# MCU.net
KiCad netlist of a schematic drawn in Altium Designer
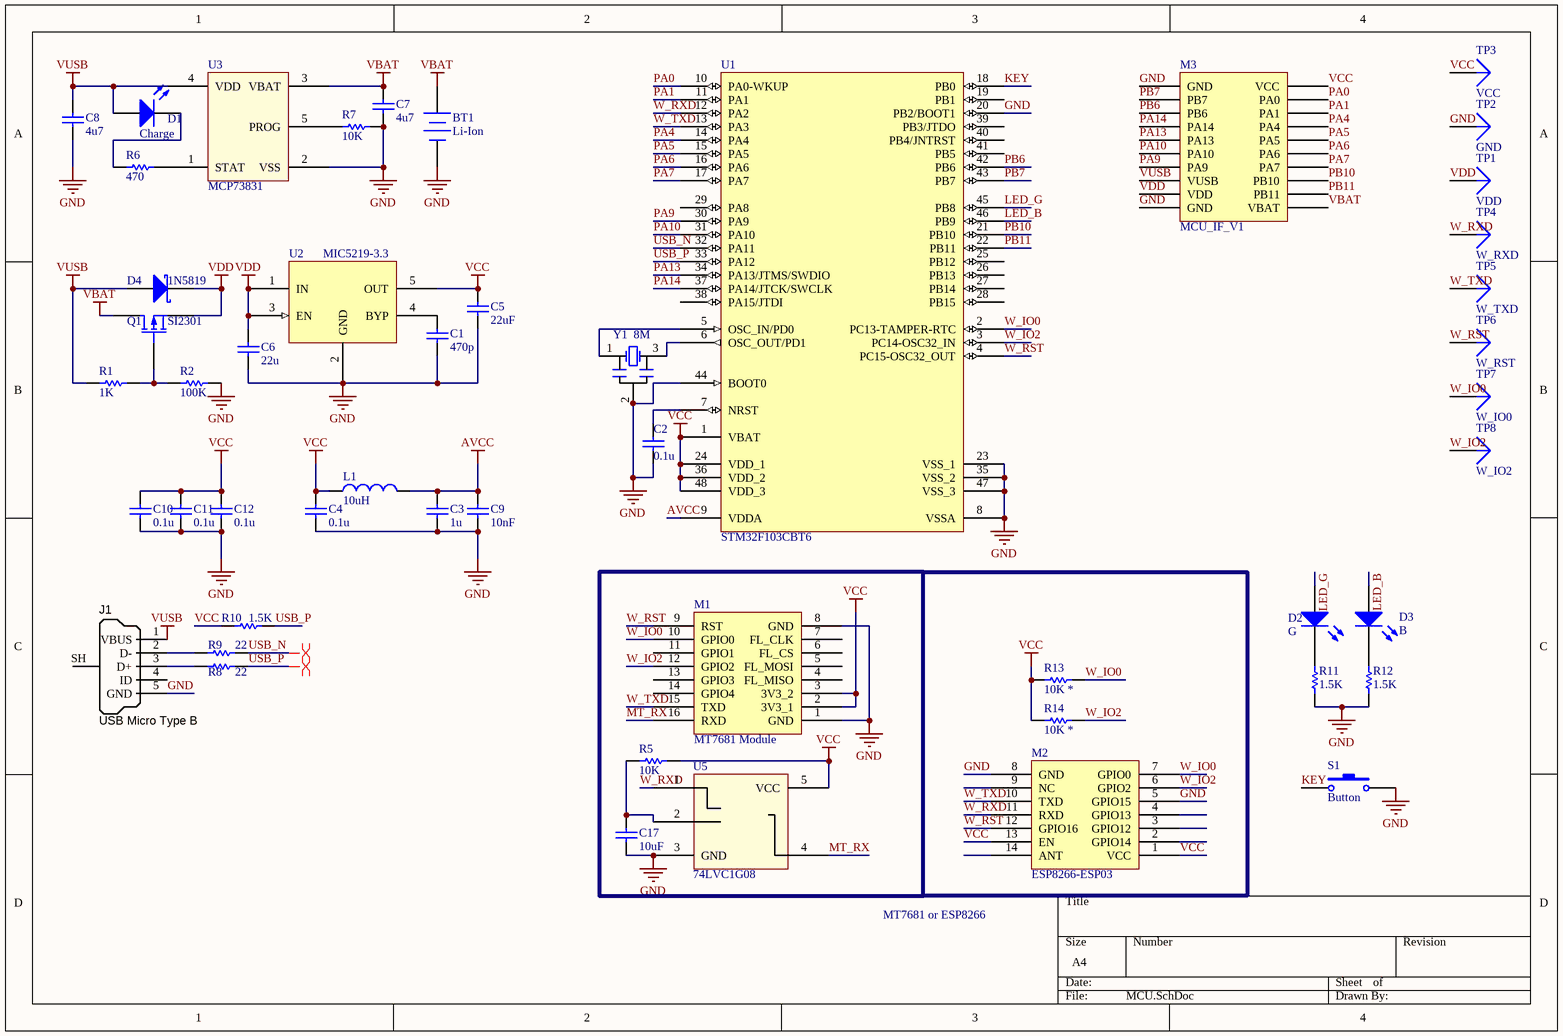
[diagram p0: MCU.SchDoc]

(export (version "E")
  (design (tool "Eeschema 10.0.6"))
  (components
    (comp (ref "BT1")
      (value "Li-Ion")
      (footprint "HDR1X2")
      (description "Multicell Battery")
      (fields (field (name "PUBLISHER") "Altium Limited"))
      (libsource (lib "Miscellaneous Devices") (part "Battery"))
    )
    (comp (ref "C1")
      (value "470p")
      (footprint "C-1608[0603]")
      (description "Capacitor (Semiconductor SIM Model)")
      (fields (field (name "Comment") "Cap Semi") (field (name "PUBLISHER") "Altium Limited"))
      (libsource (lib "Miscellaneous Devices") (part "Cap Semi"))
    )
    (comp (ref "C2")
      (value "0.1u")
      (footprint "C-1608[0603]")
      (description "Capacitor (Semiconductor SIM Model)")
      (fields (field (name "Comment") "Cap Semi") (field (name "PUBLISHER") "Altium Limited"))
      (libsource (lib "Miscellaneous Devices") (part "Cap Semi"))
    )
    (comp (ref "C3")
      (value "1u")
      (footprint "C-1608[0603]")
      (description "Capacitor (Semiconductor SIM Model)")
      (fields (field (name "Comment") "Cap Semi") (field (name "PUBLISHER") "Altium Limited"))
      (libsource (lib "Miscellaneous Devices") (part "Cap Semi"))
    )
    (comp (ref "C4")
      (value "0.1u")
      (footprint "C-1608[0603]")
      (description "Capacitor (Semiconductor SIM Model)")
      (fields (field (name "Comment") "Cap Semi") (field (name "PUBLISHER") "Altium Limited"))
      (libsource (lib "Miscellaneous Devices") (part "Cap Semi"))
    )
    (comp (ref "C5")
      (value "22uF")
      (footprint "C-2012[0805]")
      (description "Capacitor (Semiconductor SIM Model)")
      (fields (field (name "Comment") "Cap Semi") (field (name "PUBLISHER") "Altium Limited"))
      (libsource (lib "Miscellaneous Devices") (part "Cap Semi"))
    )
    (comp (ref "C6")
      (value "22u")
      (footprint "C-2012[0805]")
      (description "Capacitor (Semiconductor SIM Model)")
      (fields (field (name "Comment") "Cap Semi") (field (name "PUBLISHER") "Altium Limited"))
      (libsource (lib "Miscellaneous Devices") (part "Cap Semi"))
    )
    (comp (ref "C7")
      (value "4u7")
      (footprint "C-1608[0603]")
      (description "Capacitor (Semiconductor SIM Model)")
      (fields (field (name "Comment") "Cap Semi") (field (name "PUBLISHER") "Altium Limited"))
      (libsource (lib "Miscellaneous Devices") (part "Cap Semi"))
    )
    (comp (ref "C8")
      (value "4u7")
      (footprint "C-1608[0603]")
      (description "Capacitor (Semiconductor SIM Model)")
      (fields (field (name "Comment") "Cap Semi") (field (name "PUBLISHER") "Altium Limited"))
      (libsource (lib "Miscellaneous Devices") (part "Cap Semi"))
    )
    (comp (ref "C9")
      (value "10nF")
      (footprint "C-1608[0603]")
      (description "Capacitor (Semiconductor SIM Model)")
      (fields (field (name "Comment") "Cap Semi") (field (name "PUBLISHER") "Altium Limited"))
      (libsource (lib "Miscellaneous Devices") (part "Cap Semi"))
    )
    (comp (ref "C10")
      (value "0.1u")
      (footprint "C-1608[0603]")
      (description "Capacitor (Semiconductor SIM Model)")
      (fields (field (name "Comment") "Cap Semi") (field (name "PUBLISHER") "Altium Limited"))
      (libsource (lib "Miscellaneous Devices") (part "Cap Semi"))
    )
    (comp (ref "C11")
      (value "0.1u")
      (footprint "C-1608[0603]")
      (description "Capacitor (Semiconductor SIM Model)")
      (fields (field (name "Comment") "Cap Semi") (field (name "PUBLISHER") "Altium Limited"))
      (libsource (lib "Miscellaneous Devices") (part "Cap Semi"))
    )
    (comp (ref "C12")
      (value "0.1u")
      (footprint "C-1608[0603]")
      (description "Capacitor (Semiconductor SIM Model)")
      (fields (field (name "Comment") "Cap Semi") (field (name "PUBLISHER") "Altium Limited"))
      (libsource (lib "Miscellaneous Devices") (part "Cap Semi"))
    )
    (comp (ref "C17")
      (value "10uF")
      (footprint "C-1608[0603]")
      (description "Capacitor (Semiconductor SIM Model)")
      (fields (field (name "Comment") "Cap Semi") (field (name "PUBLISHER") "Altium Limited"))
      (libsource (lib "Miscellaneous Devices") (part "Cap Semi"))
    )
    (comp (ref "D1")
      (value "Charge")
      (footprint "LED-1608[0603]-R")
      (description "Typical RED, GREEN, YELLOW, AMBER GaAs LED")
      (fields (field (name "PUBLISHER") "Altium Limited"))
      (libsource (lib "Miscellaneous Devices") (part "LED2"))
    )
    (comp (ref "D2")
      (value "G")
      (footprint "LED-1608[0603]-G")
      (description "Typical RED, GREEN, YELLOW, AMBER GaAs LED")
      (fields (field (name "PUBLISHER") "Altium Limited"))
      (libsource (lib "Miscellaneous Devices") (part "LED2"))
    )
    (comp (ref "D3")
      (value "B")
      (footprint "LED-1608[0603]-B")
      (description "Typical RED, GREEN, YELLOW, AMBER GaAs LED")
      (fields (field (name "PUBLISHER") "Altium Limited"))
      (libsource (lib "Miscellaneous Devices") (part "LED2"))
    )
    (comp (ref "D4")
      (value "1N5819")
      (footprint "PcbLib1:SOD123")
      (description "Schottky Diode")
      (fields (field (name "PUBLISHER") "Altium Limited"))
      (libsource (lib "Miscellaneous Devices") (part "D Schottky"))
    )
    (comp (ref "J1")
      (value "USB Micro Type B")
      (footprint "MICRO USB 3D")
      (description "Connector SMD USB Micro Type B middle mount")
      (libsource (lib "Schlib1") (part "USB_Micro_TypeB"))
    )
    (comp (ref "L1")
      (value "10uH")
      (footprint "L-1608[0603]")
      (description "Inductor")
      (fields (field (name "PUBLISHER") "Altium Limited"))
      (libsource (lib "Miscellaneous Devices") (part "Inductor"))
    )
    (comp (ref "M1")
      (value "MT7681 Module")
      (footprint "MT7681-ExtAnt-1")
      (libsource (lib "WiFiMod") (part "MT7681_EXTANT_1"))
    )
    (comp (ref "M2")
      (value "ESP8266-ESP03")
      (footprint "ESP8266-ESP03")
      (libsource (lib "WiFiMod") (part "ESP8266-ESP03"))
    )
    (comp (ref "M3")
      (value "MCU_IF_V1")
      (footprint "MCU_IF_V1")
      (libsource (lib "MCU_IF") (part "MCU_IF_V1"))
    )
    (comp (ref "Q1")
      (value "SI2301")
      (footprint "SOT23B")
      (description "P-Channel MOSFET")
      (fields (field (name "PUBLISHER") "Altium Limited"))
      (libsource (lib "Miscellaneous Devices") (part "MOSFET-P"))
    )
    (comp (ref "R1")
      (value "1K")
      (footprint "R-1608[0603]")
      (description "Semiconductor Resistor")
      (fields (field (name "Comment") "Res Semi") (field (name "PUBLISHER") "Altium Limited"))
      (libsource (lib "Miscellaneous Devices") (part "Res Semi"))
    )
    (comp (ref "R2")
      (value "100K")
      (footprint "R-1608[0603]")
      (description "Semiconductor Resistor")
      (fields (field (name "Comment") "Res Semi") (field (name "PUBLISHER") "Altium Limited"))
      (libsource (lib "Miscellaneous Devices") (part "Res Semi"))
    )
    (comp (ref "R5")
      (value "10K")
      (footprint "R-1608[0603]")
      (description "Semiconductor Resistor")
      (fields (field (name "Comment") "Res Semi") (field (name "PUBLISHER") "Altium Limited"))
      (libsource (lib "Miscellaneous Devices") (part "Res Semi"))
    )
    (comp (ref "R6")
      (value "470")
      (footprint "R-1608[0603]")
      (description "Semiconductor Resistor")
      (fields (field (name "Comment") "Res Semi") (field (name "PUBLISHER") "Altium Limited"))
      (libsource (lib "Miscellaneous Devices") (part "Res Semi"))
    )
    (comp (ref "R7")
      (value "10K")
      (footprint "R-1608[0603]")
      (description "Semiconductor Resistor")
      (fields (field (name "Comment") "Res Semi") (field (name "PUBLISHER") "Altium Limited"))
      (libsource (lib "Miscellaneous Devices") (part "Res Semi"))
    )
    (comp (ref "R8")
      (value "22")
      (footprint "R-1608[0603]")
      (description "Semiconductor Resistor")
      (fields (field (name "Comment") "Res Semi") (field (name "PUBLISHER") "Altium Limited"))
      (libsource (lib "Miscellaneous Devices") (part "Res Semi"))
    )
    (comp (ref "R9")
      (value "22")
      (footprint "R-1608[0603]")
      (description "Semiconductor Resistor")
      (fields (field (name "Comment") "Res Semi") (field (name "PUBLISHER") "Altium Limited"))
      (libsource (lib "Miscellaneous Devices") (part "Res Semi"))
    )
    (comp (ref "R10")
      (value "1.5K")
      (footprint "R-1608[0603]")
      (description "Semiconductor Resistor")
      (fields (field (name "Comment") "Res Semi") (field (name "PUBLISHER") "Altium Limited"))
      (libsource (lib "Miscellaneous Devices") (part "Res Semi"))
    )
    (comp (ref "R11")
      (value "1.5K")
      (footprint "R-1608[0603]")
      (description "Semiconductor Resistor")
      (fields (field (name "Comment") "Res Semi") (field (name "PUBLISHER") "Altium Limited"))
      (libsource (lib "Miscellaneous Devices") (part "Res Semi"))
    )
    (comp (ref "R12")
      (value "1.5K")
      (footprint "R-1608[0603]")
      (description "Semiconductor Resistor")
      (fields (field (name "Comment") "Res Semi") (field (name "PUBLISHER") "Altium Limited"))
      (libsource (lib "Miscellaneous Devices") (part "Res Semi"))
    )
    (comp (ref "R13")
      (value "10K *")
      (footprint "R-1608[0603]")
      (description "Semiconductor Resistor")
      (fields (field (name "Comment") "Res Semi") (field (name "PUBLISHER") "Altium Limited"))
      (libsource (lib "Miscellaneous Devices") (part "Res Semi"))
    )
    (comp (ref "R14")
      (value "10K *")
      (footprint "R-1608[0603]")
      (description "Semiconductor Resistor")
      (fields (field (name "Comment") "Res Semi") (field (name "PUBLISHER") "Altium Limited"))
      (libsource (lib "Miscellaneous Devices") (part "Res Semi"))
    )
    (comp (ref "S1")
      (value "Button")
      (footprint "SW-2pin-SMD")
      (description "Switch")
      (fields (field (name "PUBLISHER") "Altium Limited"))
      (libsource (lib "Miscellaneous Devices") (part "SW-PB"))
    )
    (comp (ref "TP1")
      (value "VDD")
      (footprint "TESTPOINT")
      (description "Plug")
      (fields (field (name "PUBLISHER") "Altium Limited"))
      (libsource (lib "Miscellaneous Connectors") (part "Plug"))
    )
    (comp (ref "TP2")
      (value "GND")
      (footprint "TESTPOINT")
      (description "Plug")
      (fields (field (name "PUBLISHER") "Altium Limited"))
      (libsource (lib "Miscellaneous Connectors") (part "Plug"))
    )
    (comp (ref "TP3")
      (value "VCC")
      (footprint "TESTPOINT")
      (description "Plug")
      (fields (field (name "PUBLISHER") "Altium Limited"))
      (libsource (lib "Miscellaneous Connectors") (part "Plug"))
    )
    (comp (ref "TP4")
      (value "W_RXD")
      (footprint "TESTPOINT")
      (description "Plug")
      (fields (field (name "PUBLISHER") "Altium Limited"))
      (libsource (lib "Miscellaneous Connectors") (part "Plug"))
    )
    (comp (ref "TP5")
      (value "W_TXD")
      (footprint "TESTPOINT")
      (description "Plug")
      (fields (field (name "PUBLISHER") "Altium Limited"))
      (libsource (lib "Miscellaneous Connectors") (part "Plug"))
    )
    (comp (ref "TP6")
      (value "W_RST")
      (footprint "TESTPOINT")
      (description "Plug")
      (fields (field (name "PUBLISHER") "Altium Limited"))
      (libsource (lib "Miscellaneous Connectors") (part "Plug"))
    )
    (comp (ref "TP7")
      (value "W_IO0")
      (footprint "TESTPOINT")
      (description "Plug")
      (fields (field (name "PUBLISHER") "Altium Limited"))
      (libsource (lib "Miscellaneous Connectors") (part "Plug"))
    )
    (comp (ref "TP8")
      (value "W_IO2")
      (footprint "TESTPOINT")
      (description "Plug")
      (fields (field (name "PUBLISHER") "Altium Limited"))
      (libsource (lib "Miscellaneous Connectors") (part "Plug"))
    )
    (comp (ref "U1")
      (value "STM32F103CBT6")
      (footprint "LQFP48_N")
      (description "STM32 ARM-based 32-bit MCU with 128 Kbytes Flash, 48-pin LQFP, Industrial Temperature")
      (fields (field (name "PUBLISHER") "Altium Limited"))
      (libsource (lib "ST Microcontroller 32-Bit STM32") (part "STM32F103CBT6"))
    )
    (comp (ref "U2")
      (value "MIC5219-3.3")
      (footprint "SOT23-5")
      (description "500mA-Peak Output LDO Regulator")
      (libsource (lib "Schlib1") (part "MIC5219"))
    )
    (comp (ref "U3")
      (value "MCP73831")
      (footprint "SOT23-5")
      (description "Miniature Single-Cell, Fully Integrated Li-Ion, Li-Polymer Charge Management Controllers")
      (libsource (lib "MCP73831") (part "MCP73831"))
    )
    (comp (ref "U5")
      (value "74LVC1G08")
      (footprint "SOT23-5")
      (libsource (lib "74lvc1g08") (part "74LVC1G08"))
    )
    (comp (ref "Y1")
      (value "8M")
      (footprint "Crystal_C")
      (description "Crystal Oscillator")
      (fields (field (name "PUBLISHER") "Altium Limited"))
      (libsource (lib "Schlib1") (part "XTAL_C"))
    )
  )
  (nets
    (net (code "1") (name "/KEY") (class "Default")
      (node (ref "S1") (pin "1") (pinfunction "1_1") (pintype "passive"))
      (node (ref "U1") (pin "18") (pinfunction "PB0_18") (pintype "bidirectional"))
    )
    (net (code "2") (name "/LED_B") (class "Default")
      (node (ref "D3") (pin "1") (pinfunction "A_1") (pintype "passive"))
      (node (ref "U1") (pin "46") (pinfunction "PB9_46") (pintype "bidirectional"))
    )
    (net (code "3") (name "/LED_G") (class "Default")
      (node (ref "D2") (pin "1") (pinfunction "A_1") (pintype "passive"))
      (node (ref "U1") (pin "45") (pinfunction "PB8_45") (pintype "bidirectional"))
    )
    (net (code "4") (name "/MT_RX") (class "Default")
      (node (ref "M1") (pin "16") (pinfunction "RXD_16") (pintype "passive"))
      (node (ref "U5") (pin "4") (pinfunction "Y_4") (pintype "passive"))
    )
    (net (code "5") (name "/PA0") (class "Default")
      (node (ref "M3") (pin "19") (pinfunction "PA0_19") (pintype "passive"))
      (node (ref "U1") (pin "10") (pinfunction "PA0-WKUP_10") (pintype "bidirectional"))
    )
    (net (code "6") (name "/PA1") (class "Default")
      (node (ref "M3") (pin "18") (pinfunction "PA1_18") (pintype "passive"))
      (node (ref "U1") (pin "11") (pinfunction "PA1_11") (pintype "bidirectional"))
    )
    (net (code "7") (name "/PA4") (class "Default")
      (node (ref "M3") (pin "17") (pinfunction "PA4_17") (pintype "passive"))
      (node (ref "U1") (pin "14") (pinfunction "PA4_14") (pintype "bidirectional"))
    )
    (net (code "8") (name "/PA5") (class "Default")
      (node (ref "M3") (pin "16") (pinfunction "PA5_16") (pintype "passive"))
      (node (ref "U1") (pin "15") (pinfunction "PA5_15") (pintype "bidirectional"))
    )
    (net (code "9") (name "/PA6") (class "Default")
      (node (ref "M3") (pin "15") (pinfunction "PA6_15") (pintype "passive"))
      (node (ref "U1") (pin "16") (pinfunction "PA6_16") (pintype "bidirectional"))
    )
    (net (code "10") (name "/PA7") (class "Default")
      (node (ref "M3") (pin "14") (pinfunction "PA7_14") (pintype "passive"))
      (node (ref "U1") (pin "17") (pinfunction "PA7_17") (pintype "bidirectional"))
    )
    (net (code "11") (name "/PA9") (class "Default")
      (node (ref "M3") (pin "7") (pinfunction "PA9_7") (pintype "passive"))
      (node (ref "U1") (pin "30") (pinfunction "PA9_30") (pintype "bidirectional"))
    )
    (net (code "12") (name "/PA10") (class "Default")
      (node (ref "M3") (pin "6") (pinfunction "PA10_6") (pintype "passive"))
      (node (ref "U1") (pin "31") (pinfunction "PA10_31") (pintype "bidirectional"))
    )
    (net (code "13") (name "/PA13") (class "Default")
      (node (ref "M3") (pin "5") (pinfunction "PA13_5") (pintype "passive"))
      (node (ref "U1") (pin "34") (pinfunction "PA13/JTMS/SWDIO_34") (pintype "bidirectional"))
    )
    (net (code "14") (name "/PA14") (class "Default")
      (node (ref "M3") (pin "4") (pinfunction "PA14_4") (pintype "passive"))
      (node (ref "U1") (pin "37") (pinfunction "PA14/JTCK/SWCLK_37") (pintype "bidirectional"))
    )
    (net (code "15") (name "/PB6") (class "Default")
      (node (ref "M3") (pin "3") (pinfunction "PB6_3") (pintype "passive"))
      (node (ref "U1") (pin "42") (pinfunction "PB6_42") (pintype "bidirectional"))
    )
    (net (code "16") (name "/PB7") (class "Default")
      (node (ref "M3") (pin "2") (pinfunction "PB7_2") (pintype "passive"))
      (node (ref "U1") (pin "43") (pinfunction "PB7_43") (pintype "bidirectional"))
    )
    (net (code "17") (name "/PB10") (class "Default")
      (node (ref "M3") (pin "13") (pinfunction "PB10_13") (pintype "passive"))
      (node (ref "U1") (pin "21") (pinfunction "PB10_21") (pintype "bidirectional"))
    )
    (net (code "18") (name "/PB11") (class "Default")
      (node (ref "M3") (pin "12") (pinfunction "PB11_12") (pintype "passive"))
      (node (ref "U1") (pin "22") (pinfunction "PB11_22") (pintype "bidirectional"))
    )
    (net (code "19") (name "/USB_N") (class "Default")
      (node (ref "R9") (pin "2") (pinfunction "2_2") (pintype "passive"))
      (node (ref "U1") (pin "32") (pinfunction "PA11_32") (pintype "bidirectional"))
    )
    (net (code "20") (name "/USB_P") (class "Default")
      (node (ref "R10") (pin "1") (pinfunction "1_1") (pintype "passive"))
      (node (ref "R8") (pin "2") (pinfunction "2_2") (pintype "passive"))
      (node (ref "U1") (pin "33") (pinfunction "PA12_33") (pintype "bidirectional"))
    )
    (net (code "21") (name "/W_IO0") (class "Default")
      (node (ref "M1") (pin "10") (pinfunction "GPIO0_10") (pintype "passive"))
      (node (ref "M2") (pin "7") (pinfunction "GPIO0_7") (pintype "passive"))
      (node (ref "R13") (pin "2") (pinfunction "2_2") (pintype "passive"))
      (node (ref "TP7") (pin "1") (pinfunction "1_1") (pintype "passive"))
      (node (ref "U1") (pin "2") (pinfunction "PC13-TAMPER-RTC_2") (pintype "bidirectional"))
    )
    (net (code "22") (name "/W_IO2") (class "Default")
      (node (ref "M1") (pin "12") (pinfunction "GPIO2_12") (pintype "passive"))
      (node (ref "M2") (pin "6") (pinfunction "GPIO2_6") (pintype "passive"))
      (node (ref "R14") (pin "2") (pinfunction "2_2") (pintype "passive"))
      (node (ref "TP8") (pin "1") (pinfunction "1_1") (pintype "passive"))
      (node (ref "U1") (pin "3") (pinfunction "PC14-OSC32_IN_3") (pintype "bidirectional"))
    )
    (net (code "23") (name "/W_RST") (class "Default")
      (node (ref "M1") (pin "9") (pinfunction "RST_9") (pintype "passive"))
      (node (ref "M2") (pin "12") (pinfunction "GPIO16_12") (pintype "passive"))
      (node (ref "TP6") (pin "1") (pinfunction "1_1") (pintype "passive"))
      (node (ref "U1") (pin "4") (pinfunction "PC15-OSC32_OUT_4") (pintype "bidirectional"))
    )
    (net (code "24") (name "/W_RXD") (class "Default")
      (node (ref "M2") (pin "11") (pinfunction "RXD_11") (pintype "passive"))
      (node (ref "TP4") (pin "1") (pinfunction "1_1") (pintype "passive"))
      (node (ref "U1") (pin "12") (pinfunction "PA2_12") (pintype "bidirectional"))
      (node (ref "U5") (pin "1") (pinfunction "B_1") (pintype "passive"))
    )
    (net (code "25") (name "/W_TXD") (class "Default")
      (node (ref "M1") (pin "15") (pinfunction "TXD_15") (pintype "passive"))
      (node (ref "M2") (pin "10") (pinfunction "TXD_10") (pintype "passive"))
      (node (ref "TP5") (pin "1") (pinfunction "1_1") (pintype "passive"))
      (node (ref "U1") (pin "13") (pinfunction "PA3_13") (pintype "bidirectional"))
    )
    (net (code "26") (name "AVCC") (class "Default")
      (node (ref "C3") (pin "2") (pinfunction "2_2") (pintype "passive"))
      (node (ref "C9") (pin "2") (pinfunction "2_2") (pintype "passive"))
      (node (ref "L1") (pin "2") (pinfunction "2_2") (pintype "passive"))
      (node (ref "U1") (pin "9") (pinfunction "VDDA_9") (pintype "power_in"))
    )
    (net (code "27") (name "GND") (class "Default")
      (node (ref "BT1") (pin "2") (pinfunction "-_2") (pintype "passive"))
      (node (ref "C1") (pin "2") (pinfunction "2_2") (pintype "passive"))
      (node (ref "C10") (pin "1") (pinfunction "1_1") (pintype "passive"))
      (node (ref "C11") (pin "1") (pinfunction "1_1") (pintype "passive"))
      (node (ref "C12") (pin "1") (pinfunction "1_1") (pintype "passive"))
      (node (ref "C17") (pin "1") (pinfunction "1_1") (pintype "passive"))
      (node (ref "C2") (pin "1") (pinfunction "1_1") (pintype "passive"))
      (node (ref "C3") (pin "1") (pinfunction "1_1") (pintype "passive"))
      (node (ref "C4") (pin "1") (pinfunction "1_1") (pintype "passive"))
      (node (ref "C5") (pin "2") (pinfunction "2_2") (pintype "passive"))
      (node (ref "C6") (pin "2") (pinfunction "2_2") (pintype "passive"))
      (node (ref "C7") (pin "1") (pinfunction "1_1") (pintype "passive"))
      (node (ref "C8") (pin "1") (pinfunction "1_1") (pintype "passive"))
      (node (ref "C9") (pin "1") (pinfunction "1_1") (pintype "passive"))
      (node (ref "J1") (pin "5") (pinfunction "GND_5") (pintype "passive"))
      (node (ref "M1") (pin "1") (pinfunction "GND_1") (pintype "passive"))
      (node (ref "M1") (pin "8") (pinfunction "GND_8") (pintype "passive"))
      (node (ref "M2") (pin "5") (pinfunction "GPIO15_5") (pintype "passive"))
      (node (ref "M2") (pin "8") (pinfunction "GND_8") (pintype "passive"))
      (node (ref "M3") (pin "1") (pinfunction "GND_1") (pintype "passive"))
      (node (ref "M3") (pin "10") (pinfunction "GND_10") (pintype "passive"))
      (node (ref "R11") (pin "2") (pinfunction "2_2") (pintype "passive"))
      (node (ref "R12") (pin "2") (pinfunction "2_2") (pintype "passive"))
      (node (ref "R2") (pin "2") (pinfunction "2_2") (pintype "passive"))
      (node (ref "R7") (pin "1") (pinfunction "1_1") (pintype "passive"))
      (node (ref "S1") (pin "2") (pinfunction "2_2") (pintype "passive"))
      (node (ref "TP2") (pin "1") (pinfunction "1_1") (pintype "passive"))
      (node (ref "U1") (pin "20") (pinfunction "PB2/BOOT1_20") (pintype "bidirectional"))
      (node (ref "U1") (pin "23") (pinfunction "VSS_1_23") (pintype "power_in"))
      (node (ref "U1") (pin "35") (pinfunction "VSS_2_35") (pintype "power_in"))
      (node (ref "U1") (pin "44") (pinfunction "BOOT0_44") (pintype "input"))
      (node (ref "U1") (pin "47") (pinfunction "VSS_3_47") (pintype "power_in"))
      (node (ref "U1") (pin "8") (pinfunction "VSSA_8") (pintype "power_in"))
      (node (ref "U2") (pin "2") (pinfunction "GND_2") (pintype "passive"))
      (node (ref "U3") (pin "2") (pinfunction "VSS_2") (pintype "passive"))
      (node (ref "U5") (pin "3") (pinfunction "GND_3") (pintype "passive"))
      (node (ref "Y1") (pin "2") (pinfunction "GND_2") (pintype "passive"))
    )
    (net (code "28") (name "Net-(D1-K)") (class "Default")
      (node (ref "D1") (pin "2") (pinfunction "K_2") (pintype "passive"))
      (node (ref "R6") (pin "1") (pinfunction "1_1") (pintype "passive"))
    )
    (net (code "29") (name "Net-(D2-K)") (class "Default")
      (node (ref "D2") (pin "2") (pinfunction "K_2") (pintype "passive"))
      (node (ref "R11") (pin "1") (pinfunction "1_1") (pintype "passive"))
    )
    (net (code "30") (name "Net-(D3-K)") (class "Default")
      (node (ref "D3") (pin "2") (pinfunction "K_2") (pintype "passive"))
      (node (ref "R12") (pin "1") (pinfunction "1_1") (pintype "passive"))
    )
    (net (code "31") (name "Net-(J1-D+)") (class "Default")
      (node (ref "J1") (pin "3") (pinfunction "D+_3") (pintype "passive"))
      (node (ref "R8") (pin "1") (pinfunction "1_1") (pintype "passive"))
    )
    (net (code "32") (name "Net-(J1-D-)") (class "Default")
      (node (ref "J1") (pin "2") (pinfunction "D-_2") (pintype "passive"))
      (node (ref "R9") (pin "1") (pinfunction "1_1") (pintype "passive"))
    )
    (net (code "33") (name "Net-(Q1-G)") (class "Default")
      (node (ref "Q1") (pin "2") (pinfunction "G_2") (pintype "passive"))
      (node (ref "R1") (pin "2") (pinfunction "2_2") (pintype "passive"))
      (node (ref "R2") (pin "1") (pinfunction "1_1") (pintype "passive"))
    )
    (net (code "34") (name "Net-(U1-NRST)") (class "Default")
      (node (ref "C2") (pin "2") (pinfunction "2_2") (pintype "passive"))
      (node (ref "U1") (pin "7") (pinfunction "NRST_7") (pintype "bidirectional"))
    )
    (net (code "35") (name "Net-(U1-OSC_IN{slash}PD0)") (class "Default")
      (node (ref "U1") (pin "5") (pinfunction "OSC_IN/PD0_5") (pintype "input"))
      (node (ref "Y1") (pin "1") (pinfunction "OSC1_1") (pintype "passive"))
    )
    (net (code "36") (name "Net-(U1-OSC_OUT{slash}PD1)") (class "Default")
      (node (ref "U1") (pin "6") (pinfunction "OSC_OUT/PD1_6") (pintype "output"))
      (node (ref "Y1") (pin "3") (pinfunction "OSC2_3") (pintype "passive"))
    )
    (net (code "37") (name "Net-(U2-BYP)") (class "Default")
      (node (ref "C1") (pin "1") (pinfunction "1_1") (pintype "passive"))
      (node (ref "U2") (pin "4") (pinfunction "BYP_4") (pintype "passive"))
    )
    (net (code "38") (name "Net-(U3-PROG)") (class "Default")
      (node (ref "R7") (pin "2") (pinfunction "2_2") (pintype "passive"))
      (node (ref "U3") (pin "5") (pinfunction "PROG_5") (pintype "passive"))
    )
    (net (code "39") (name "Net-(U3-STAT)") (class "Default")
      (node (ref "R6") (pin "2") (pinfunction "2_2") (pintype "passive"))
      (node (ref "U3") (pin "1") (pinfunction "STAT_1") (pintype "passive"))
    )
    (net (code "40") (name "Net-(U5-A)") (class "Default")
      (node (ref "C17") (pin "2") (pinfunction "2_2") (pintype "passive"))
      (node (ref "R5") (pin "2") (pinfunction "2_2") (pintype "passive"))
      (node (ref "U5") (pin "2") (pinfunction "A_2") (pintype "passive"))
    )
    (net (code "41") (name "VBAT") (class "Default")
      (node (ref "BT1") (pin "1") (pinfunction "+_1") (pintype "passive"))
      (node (ref "C7") (pin "2") (pinfunction "2_2") (pintype "passive"))
      (node (ref "M3") (pin "11") (pinfunction "VBAT_11") (pintype "passive"))
      (node (ref "Q1") (pin "1") (pinfunction "D_1") (pintype "passive"))
      (node (ref "U3") (pin "3") (pinfunction "VBAT_3") (pintype "passive"))
    )
    (net (code "42") (name "VCC") (class "Default")
      (node (ref "C10") (pin "2") (pinfunction "2_2") (pintype "passive"))
      (node (ref "C11") (pin "2") (pinfunction "2_2") (pintype "passive"))
      (node (ref "C12") (pin "2") (pinfunction "2_2") (pintype "passive"))
      (node (ref "C4") (pin "2") (pinfunction "2_2") (pintype "passive"))
      (node (ref "C5") (pin "1") (pinfunction "1_1") (pintype "passive"))
      (node (ref "L1") (pin "1") (pinfunction "1_1") (pintype "passive"))
      (node (ref "M1") (pin "2") (pinfunction "3V3_1_2") (pintype "passive"))
      (node (ref "M1") (pin "3") (pinfunction "3V3_2_3") (pintype "passive"))
      (node (ref "M2") (pin "1") (pinfunction "VCC_1") (pintype "passive"))
      (node (ref "M2") (pin "13") (pinfunction "EN_13") (pintype "passive"))
      (node (ref "M3") (pin "20") (pinfunction "VCC_20") (pintype "passive"))
      (node (ref "R10") (pin "2") (pinfunction "2_2") (pintype "passive"))
      (node (ref "R13") (pin "1") (pinfunction "1_1") (pintype "passive"))
      (node (ref "R14") (pin "1") (pinfunction "1_1") (pintype "passive"))
      (node (ref "R5") (pin "1") (pinfunction "1_1") (pintype "passive"))
      (node (ref "TP3") (pin "1") (pinfunction "1_1") (pintype "passive"))
      (node (ref "U1") (pin "1") (pinfunction "VBAT_1") (pintype "power_in"))
      (node (ref "U1") (pin "24") (pinfunction "VDD_1_24") (pintype "power_in"))
      (node (ref "U1") (pin "36") (pinfunction "VDD_2_36") (pintype "power_in"))
      (node (ref "U1") (pin "48") (pinfunction "VDD_3_48") (pintype "power_in"))
      (node (ref "U2") (pin "5") (pinfunction "OUT_5") (pintype "passive"))
      (node (ref "U5") (pin "5") (pinfunction "VCC_5") (pintype "passive"))
    )
    (net (code "43") (name "VDD") (class "Default")
      (node (ref "C6") (pin "1") (pinfunction "1_1") (pintype "passive"))
      (node (ref "D4") (pin "2") (pinfunction "K_2") (pintype "passive"))
      (node (ref "M3") (pin "9") (pinfunction "VDD_9") (pintype "passive"))
      (node (ref "Q1") (pin "3") (pinfunction "S_3") (pintype "passive"))
      (node (ref "TP1") (pin "1") (pinfunction "1_1") (pintype "passive"))
      (node (ref "U2") (pin "1") (pinfunction "IN_1") (pintype "power_in"))
      (node (ref "U2") (pin "3") (pinfunction "EN_3") (pintype "input"))
    )
    (net (code "44") (name "VUSB") (class "Default")
      (node (ref "C8") (pin "2") (pinfunction "2_2") (pintype "passive"))
      (node (ref "D1") (pin "1") (pinfunction "A_1") (pintype "passive"))
      (node (ref "D4") (pin "1") (pinfunction "A_1") (pintype "passive"))
      (node (ref "J1") (pin "1") (pinfunction "VBUS_1") (pintype "passive"))
      (node (ref "M3") (pin "8") (pinfunction "VUSB_8") (pintype "passive"))
      (node (ref "R1") (pin "1") (pinfunction "1_1") (pintype "passive"))
      (node (ref "U3") (pin "4") (pinfunction "VDD_4") (pintype "passive"))
    )
    (net (code "45") (name "unconnected-(J1-ID-Pad4)") (class "Default")
      (node (ref "J1") (pin "4") (pinfunction "ID_4") (pintype "passive"))
    )
    (net (code "46") (name "unconnected-(J1-Shell-PadSH)") (class "Default")
      (node (ref "J1") (pin "SH") (pinfunction "Shell_SH") (pintype "passive"))
    )
    (net (code "47") (name "unconnected-(M1-FL_CLK-Pad7)") (class "Default")
      (node (ref "M1") (pin "7") (pinfunction "FL_CLK_7") (pintype "passive"))
    )
    (net (code "48") (name "unconnected-(M1-FL_CS-Pad6)") (class "Default")
      (node (ref "M1") (pin "6") (pinfunction "FL_CS_6") (pintype "passive"))
    )
    (net (code "49") (name "unconnected-(M1-FL_MISO-Pad4)") (class "Default")
      (node (ref "M1") (pin "4") (pinfunction "FL_MISO_4") (pintype "passive"))
    )
    (net (code "50") (name "unconnected-(M1-FL_MOSI-Pad5)") (class "Default")
      (node (ref "M1") (pin "5") (pinfunction "FL_MOSI_5") (pintype "passive"))
    )
    (net (code "51") (name "unconnected-(M1-GPIO1-Pad11)") (class "Default")
      (node (ref "M1") (pin "11") (pinfunction "GPIO1_11") (pintype "passive"))
    )
    (net (code "52") (name "unconnected-(M1-GPIO3-Pad13)") (class "Default")
      (node (ref "M1") (pin "13") (pinfunction "GPIO3_13") (pintype "passive"))
    )
    (net (code "53") (name "unconnected-(M1-GPIO4-Pad14)") (class "Default")
      (node (ref "M1") (pin "14") (pinfunction "GPIO4_14") (pintype "passive"))
    )
    (net (code "54") (name "unconnected-(M2-ANT-Pad14)") (class "Default")
      (node (ref "M2") (pin "14") (pinfunction "ANT_14") (pintype "passive"))
    )
    (net (code "55") (name "unconnected-(M2-GPIO12-Pad3)") (class "Default")
      (node (ref "M2") (pin "3") (pinfunction "GPIO12_3") (pintype "passive"))
    )
    (net (code "56") (name "unconnected-(M2-GPIO13-Pad4)") (class "Default")
      (node (ref "M2") (pin "4") (pinfunction "GPIO13_4") (pintype "passive"))
    )
    (net (code "57") (name "unconnected-(M2-GPIO14-Pad2)") (class "Default")
      (node (ref "M2") (pin "2") (pinfunction "GPIO14_2") (pintype "passive"))
    )
    (net (code "58") (name "unconnected-(M2-NC-Pad9)") (class "Default")
      (node (ref "M2") (pin "9") (pinfunction "NC_9") (pintype "passive"))
    )
    (net (code "59") (name "unconnected-(U1-PA8-Pad29)") (class "Default")
      (node (ref "U1") (pin "29") (pinfunction "PA8_29") (pintype "bidirectional"))
    )
    (net (code "60") (name "unconnected-(U1-PA15{slash}JTDI-Pad38)") (class "Default")
      (node (ref "U1") (pin "38") (pinfunction "PA15/JTDI_38") (pintype "bidirectional"))
    )
    (net (code "61") (name "unconnected-(U1-PB1-Pad19)") (class "Default")
      (node (ref "U1") (pin "19") (pinfunction "PB1_19") (pintype "bidirectional"))
    )
    (net (code "62") (name "unconnected-(U1-PB3{slash}JTDO-Pad39)") (class "Default")
      (node (ref "U1") (pin "39") (pinfunction "PB3/JTDO_39") (pintype "bidirectional"))
    )
    (net (code "63") (name "unconnected-(U1-PB4{slash}JNTRST-Pad40)") (class "Default")
      (node (ref "U1") (pin "40") (pinfunction "PB4/JNTRST_40") (pintype "bidirectional"))
    )
    (net (code "64") (name "unconnected-(U1-PB5-Pad41)") (class "Default")
      (node (ref "U1") (pin "41") (pinfunction "PB5_41") (pintype "bidirectional"))
    )
    (net (code "65") (name "unconnected-(U1-PB12-Pad25)") (class "Default")
      (node (ref "U1") (pin "25") (pinfunction "PB12_25") (pintype "bidirectional"))
    )
    (net (code "66") (name "unconnected-(U1-PB13-Pad26)") (class "Default")
      (node (ref "U1") (pin "26") (pinfunction "PB13_26") (pintype "bidirectional"))
    )
    (net (code "67") (name "unconnected-(U1-PB14-Pad27)") (class "Default")
      (node (ref "U1") (pin "27") (pinfunction "PB14_27") (pintype "bidirectional"))
    )
    (net (code "68") (name "unconnected-(U1-PB15-Pad28)") (class "Default")
      (node (ref "U1") (pin "28") (pinfunction "PB15_28") (pintype "bidirectional"))
    )
  )
)
